# hat.net
KiCad netlist of a schematic drawn in EAGLE
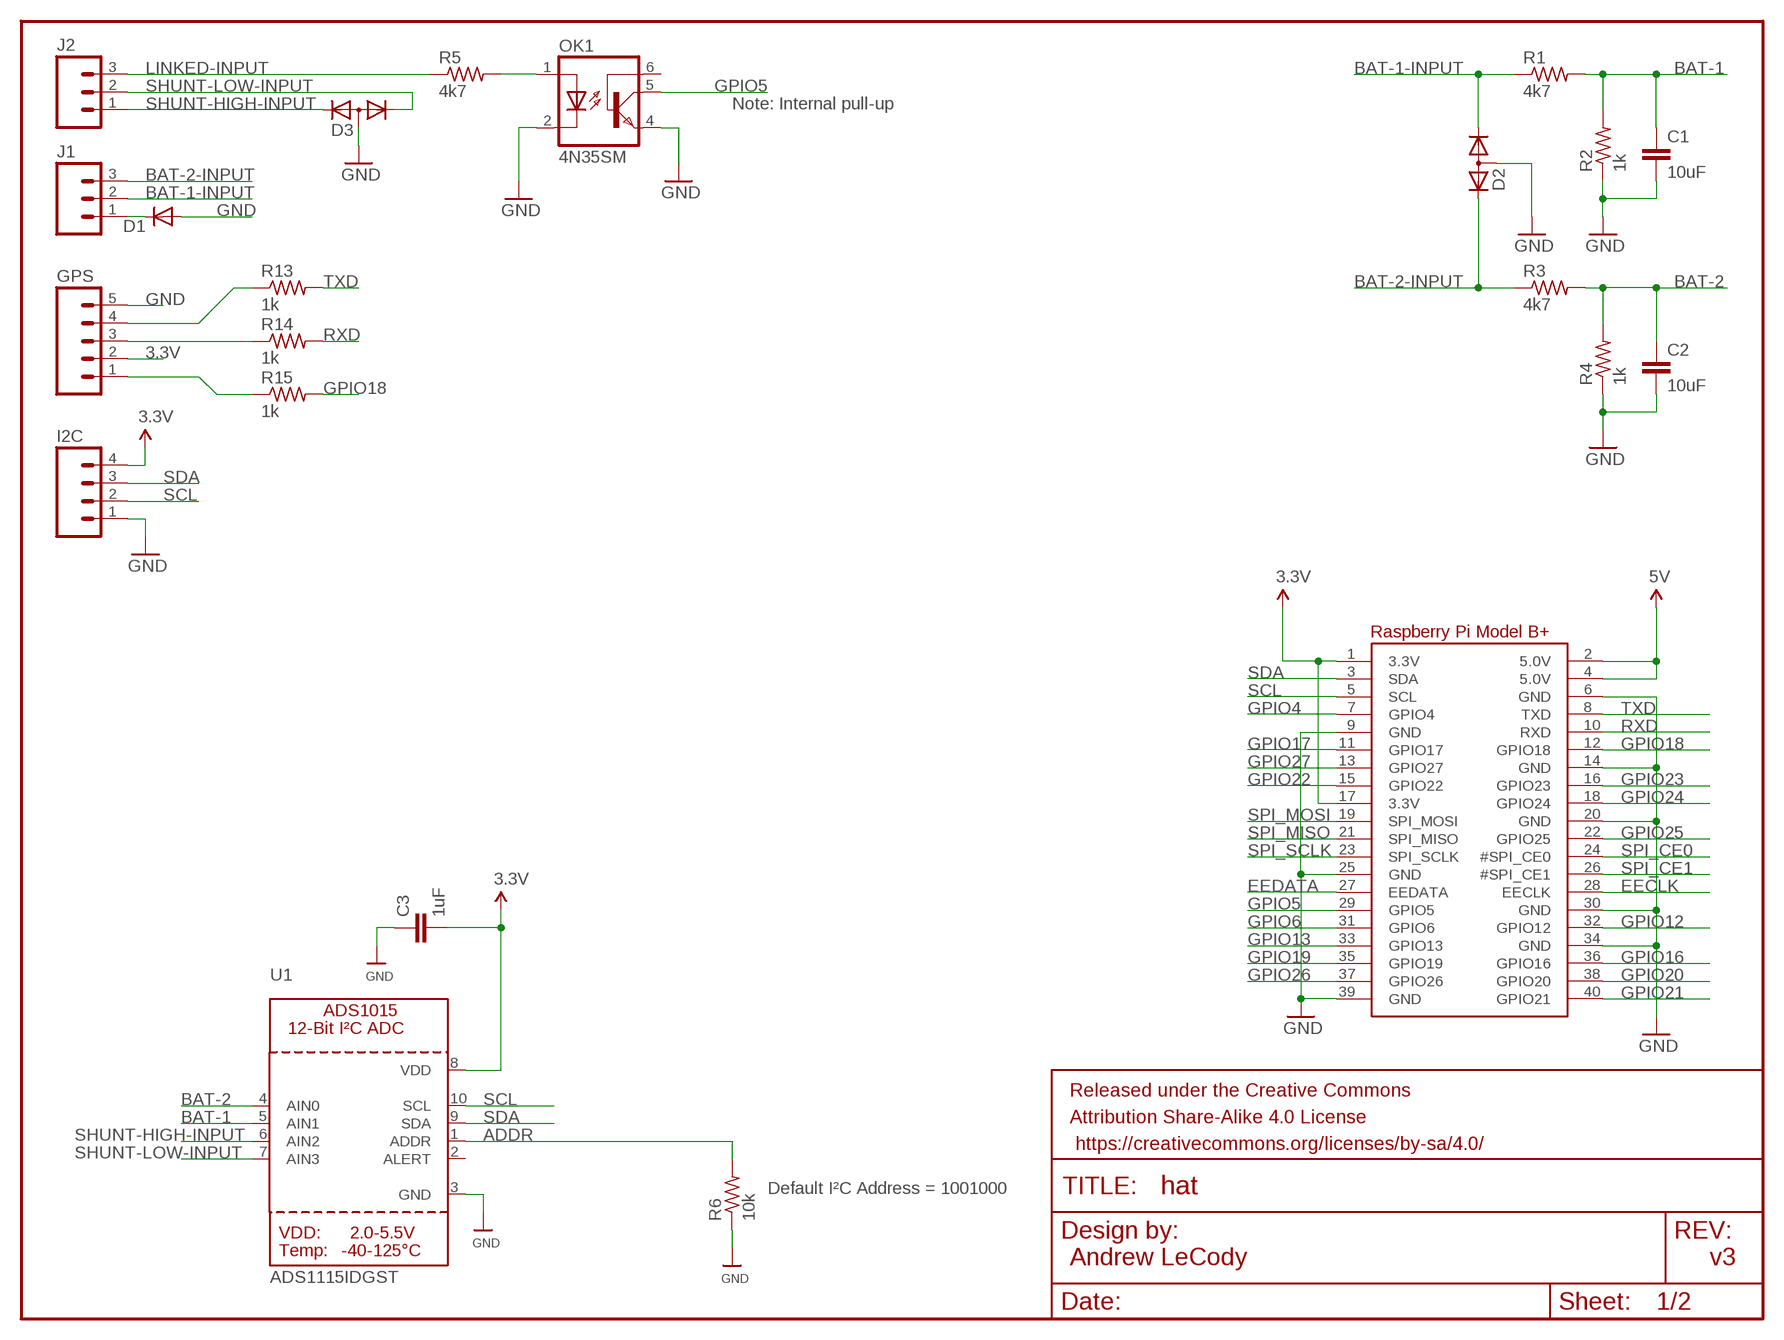
[diagram p0: schematic, sheet 1]
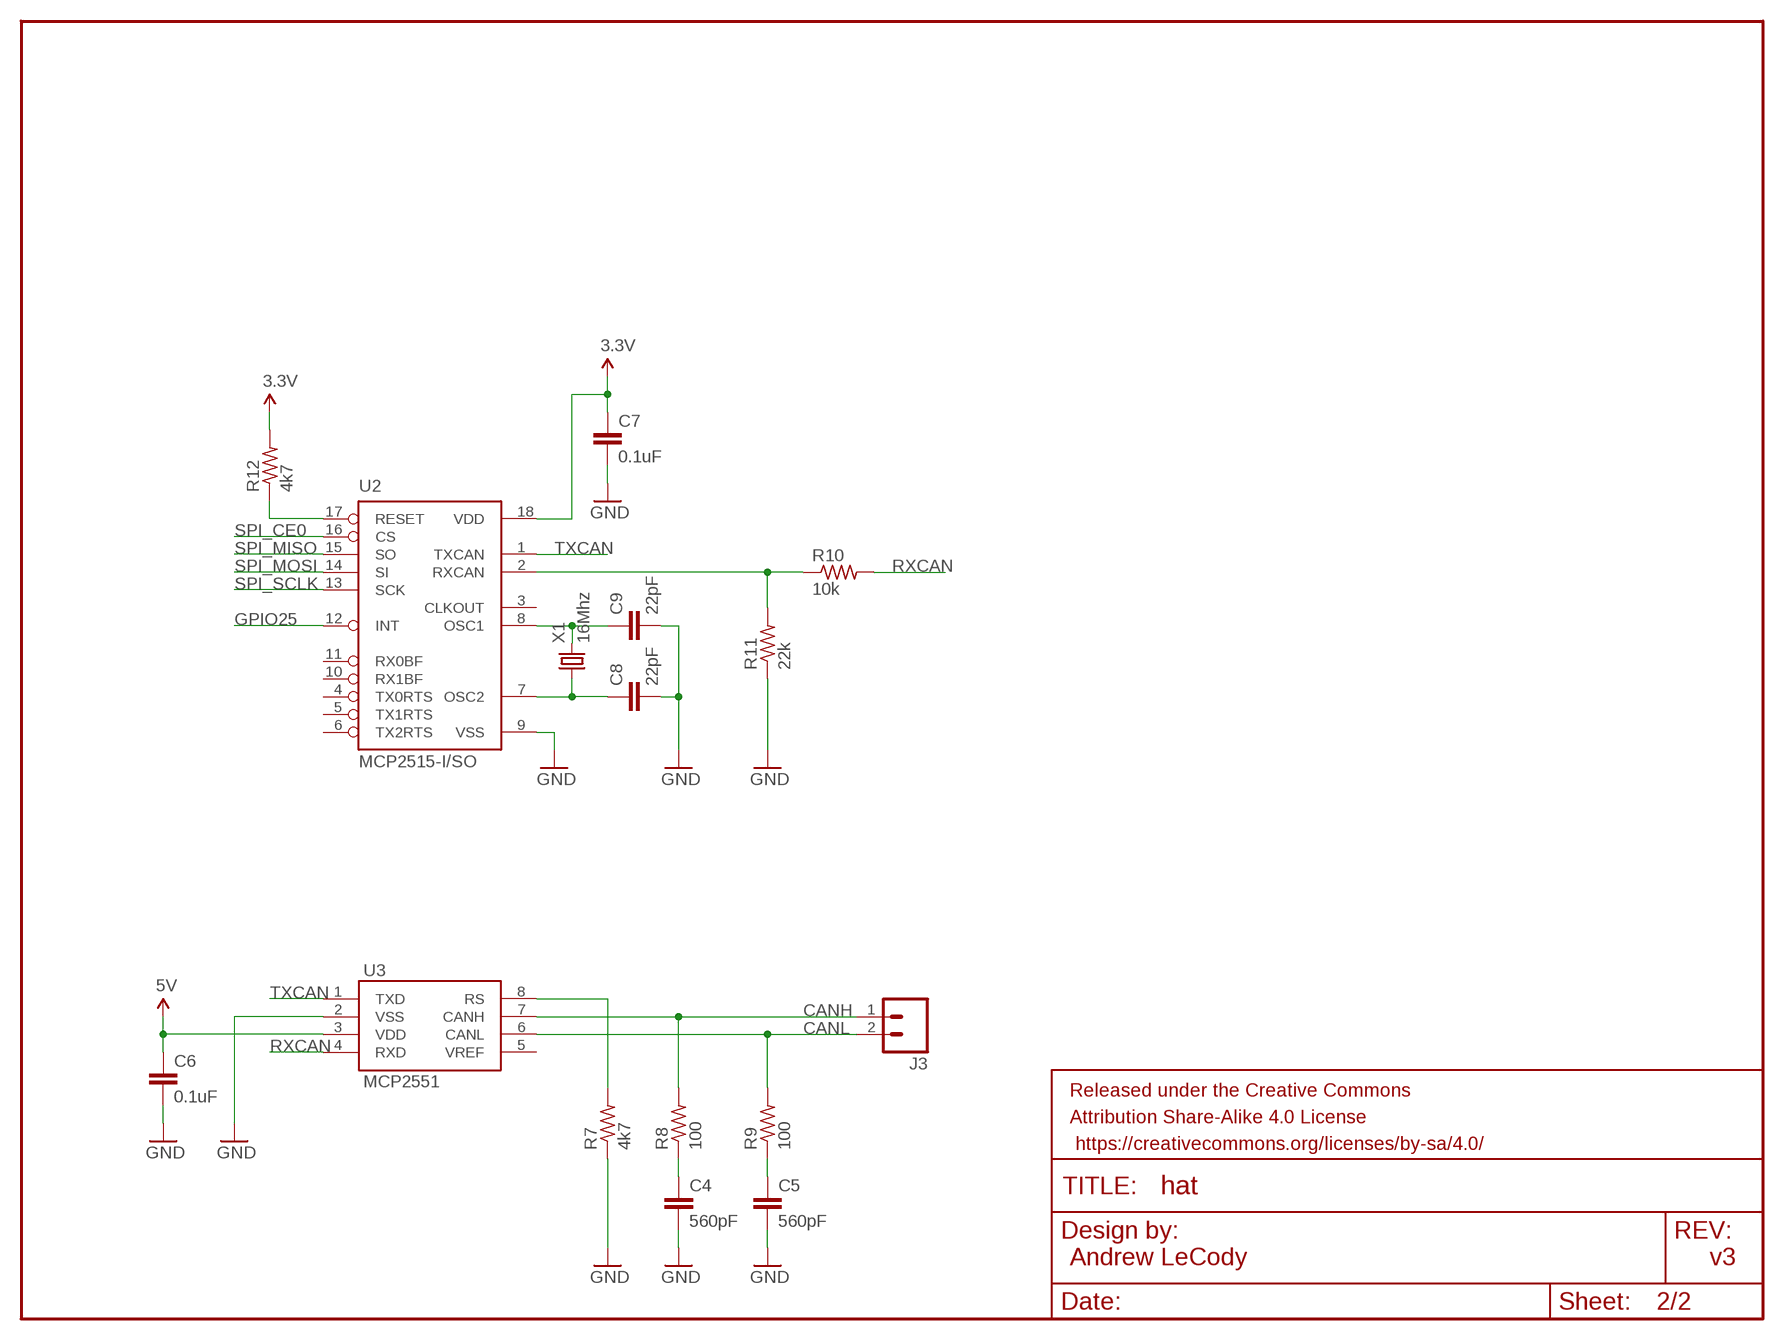
[diagram p1: schematic, sheet 2]

(export (version "E")
  (design (tool "Eeschema 10.0.6"))
  (components
    (comp (ref "C1")
      (value "10uF")
      (footprint "eagle-import:C0805")
      (libsource (lib "eagle-import") (part "CAPACITOR_C0805"))
    )
    (comp (ref "C2")
      (value "10uF")
      (footprint "eagle-import:C0805")
      (libsource (lib "eagle-import") (part "CAPACITOR_C0805"))
    )
    (comp (ref "C3")
      (value "1uF")
      (footprint "eagle-import:C0805")
      (libsource (lib "eagle-import") (part "CAPACITOR_C0805"))
    )
    (comp (ref "D1")
      (value "DIODE-DO214AC")
      (footprint "eagle-import:DO214AC")
      (libsource (lib "eagle-import") (part "DIODE-DO214AC"))
    )
    (comp (ref "D2")
      (value "DIODE-2CA|ACSOT23")
      (footprint "eagle-import:SOT23")
      (libsource (lib "eagle-import") (part "DIODE-2CA|ACSOT23"))
    )
    (comp (ref "D3")
      (value "DIODE-2CA|ACSOT23")
      (footprint "eagle-import:SOT23")
      (libsource (lib "eagle-import") (part "DIODE-2CA|ACSOT23"))
    )
    (comp (ref "FRAME1")
      (value "FRAME-LETTERNO_PACKAGE")
      (footprint "eagle-import:DUMMY")
      (fields (field (name "DESIGNER") "Nobody"))
      (libsource (lib "eagle-import") (part "FRAME-LETTERNO_PACKAGE"))
    )
    (comp (ref "GPS")
      (value "M05PTH")
      (footprint "eagle-import:1X05")
      (libsource (lib "eagle-import") (part "M05PTH"))
    )
    (comp (ref "I2C")
      (value "M04PTH")
      (footprint "eagle-import:1X04")
      (libsource (lib "eagle-import") (part "M04PTH"))
    )
    (comp (ref "J1")
      (value "M03SCREW")
      (footprint "eagle-import:SCREWTERMINAL-3.5MM-3")
      (libsource (lib "eagle-import") (part "M03SCREW"))
    )
    (comp (ref "J2")
      (value "M03SCREW")
      (footprint "eagle-import:SCREWTERMINAL-3.5MM-3")
      (libsource (lib "eagle-import") (part "M03SCREW"))
    )
    (comp (ref "OK1")
      (value "4N35SM")
      (footprint "eagle-import:DIL6-SMD")
      (fields (field (name "MF") "FAIRCHILD SEMICONDUCTOR") (field (name "MPN") "4N35S-M"))
      (libsource (lib "eagle-import") (part "4N?MS35"))
    )
    (comp (ref "R1")
      (value "4k7")
      (footprint "eagle-import:R0805")
      (libsource (lib "eagle-import") (part "aceat64-resistor_RESISTOR_R0805"))
    )
    (comp (ref "R2")
      (value "1k")
      (footprint "eagle-import:R0805")
      (libsource (lib "eagle-import") (part "aceat64-resistor_RESISTOR_R0805"))
    )
    (comp (ref "R3")
      (value "4k7")
      (footprint "eagle-import:R0805")
      (libsource (lib "eagle-import") (part "aceat64-resistor_RESISTOR_R0805"))
    )
    (comp (ref "R4")
      (value "1k")
      (footprint "eagle-import:R0805")
      (libsource (lib "eagle-import") (part "aceat64-resistor_RESISTOR_R0805"))
    )
    (comp (ref "R5")
      (value "4k7")
      (footprint "eagle-import:R0805")
      (libsource (lib "eagle-import") (part "RESISTOR_R0805"))
    )
    (comp (ref "R6")
      (value "10k")
      (footprint "eagle-import:R0805")
      (libsource (lib "eagle-import") (part "RESISTOR_R0805"))
    )
    (comp (ref "R13")
      (value "1k")
      (footprint "eagle-import:R0805")
      (libsource (lib "eagle-import") (part "RESISTOR_R0805"))
    )
    (comp (ref "R14")
      (value "1k")
      (footprint "eagle-import:R0805")
      (libsource (lib "eagle-import") (part "RESISTOR_R0805"))
    )
    (comp (ref "R15")
      (value "1k")
      (footprint "eagle-import:R0805")
      (libsource (lib "eagle-import") (part "RESISTOR_R0805"))
    )
    (comp (ref "RPI1")
      (value "RASPBERRYPI_BPLUS_HATNOSLOTS")
      (footprint "eagle-import:PI_HAT_NOSLOTS")
      (libsource (lib "eagle-import") (part "RASPBERRYPI_BPLUS_HATNOSLOTS"))
    )
    (comp (ref "U1")
      (value "ADS1115IDGST")
      (footprint "eagle-import:MSOP10")
      (libsource (lib "eagle-import") (part "ADC_ADS1015"))
    )
    (comp (ref "C4")
      (value "560pF")
      (footprint "eagle-import:C0805")
      (libsource (lib "eagle-import") (part "CAPACITOR_C0805"))
    )
    (comp (ref "C5")
      (value "560pF")
      (footprint "eagle-import:C0805")
      (libsource (lib "eagle-import") (part "CAPACITOR_C0805"))
    )
    (comp (ref "C6")
      (value "0.1uF")
      (footprint "eagle-import:C0805")
      (libsource (lib "eagle-import") (part "CAPACITOR_C0805"))
    )
    (comp (ref "C7")
      (value "0.1uF")
      (footprint "eagle-import:C0805")
      (libsource (lib "eagle-import") (part "CAPACITOR_C0805"))
    )
    (comp (ref "C8")
      (value "22pF")
      (footprint "eagle-import:C0805")
      (libsource (lib "eagle-import") (part "CAPACITOR_C0805"))
    )
    (comp (ref "C9")
      (value "22pF")
      (footprint "eagle-import:C0805")
      (libsource (lib "eagle-import") (part "CAPACITOR_C0805"))
    )
    (comp (ref "FRAME2")
      (value "FRAME-LETTERNO_PACKAGE")
      (footprint "eagle-import:DUMMY")
      (fields (field (name "DESIGNER") "Nobody"))
      (libsource (lib "eagle-import") (part "FRAME-LETTERNO_PACKAGE"))
    )
    (comp (ref "J3")
      (value "M023.5MM")
      (footprint "eagle-import:SCREWTERMINAL-3.5MM-2")
      (libsource (lib "eagle-import") (part "M023.5MM"))
    )
    (comp (ref "R7")
      (value "4k7")
      (footprint "eagle-import:R0805")
      (libsource (lib "eagle-import") (part "RESISTOR_R0805"))
    )
    (comp (ref "R8")
      (value "100")
      (footprint "eagle-import:R0805")
      (libsource (lib "eagle-import") (part "RESISTOR_R0805"))
    )
    (comp (ref "R9")
      (value "100")
      (footprint "eagle-import:R0805")
      (libsource (lib "eagle-import") (part "RESISTOR_R0805"))
    )
    (comp (ref "R10")
      (value "10k")
      (footprint "eagle-import:R0805")
      (libsource (lib "eagle-import") (part "RESISTOR_R0805"))
    )
    (comp (ref "R11")
      (value "22k")
      (footprint "eagle-import:R0805")
      (libsource (lib "eagle-import") (part "RESISTOR_R0805"))
    )
    (comp (ref "R12")
      (value "4k7")
      (footprint "eagle-import:R0805")
      (libsource (lib "eagle-import") (part "RESISTOR_R0805"))
    )
    (comp (ref "U2")
      (value "MCP2515-I/SO")
      (footprint "eagle-import:SO18L")
      (libsource (lib "eagle-import") (part "MCP2515-I/SO"))
    )
    (comp (ref "U3")
      (value "MCP2551")
      (footprint "eagle-import:SO08")
      (libsource (lib "eagle-import") (part "MCP2551"))
    )
    (comp (ref "X1")
      (value "16Mhz")
      (footprint "eagle-import:HC49-4-HSMX")
      (libsource (lib "eagle-import") (part "CRYSTALS-NOGND-4-HSMX"))
    )
  )
  (nets
    (net (code "1") (name "3.3V") (class "Default")
      (node (ref "C3") (pin "2") (pinfunction "2_2") (pintype "passive"))
      (node (ref "C7") (pin "1") (pinfunction "1_1") (pintype "passive"))
      (node (ref "GPS") (pin "2") (pinfunction "2_2") (pintype "passive"))
      (node (ref "I2C") (pin "4") (pinfunction "4_4") (pintype "passive"))
      (node (ref "R12") (pin "2") (pinfunction "2_2") (pintype "passive"))
      (node (ref "RPI1") (pin "1") (pinfunction "3.3V_1") (pintype "power_in"))
      (node (ref "RPI1") (pin "17") (pinfunction "3.3V_17") (pintype "power_in"))
      (node (ref "U1") (pin "8") (pinfunction "VDD_8") (pintype "bidirectional"))
      (node (ref "U2") (pin "18") (pinfunction "VDD_18") (pintype "power_in"))
    )
    (net (code "2") (name "5V") (class "Default")
      (node (ref "C6") (pin "1") (pinfunction "1_1") (pintype "passive"))
      (node (ref "RPI1") (pin "2") (pinfunction "5.0V_2") (pintype "power_in"))
      (node (ref "RPI1") (pin "4") (pinfunction "5.0V_4") (pintype "power_in"))
      (node (ref "U3") (pin "3") (pinfunction "VDD_3") (pintype "bidirectional"))
    )
    (net (code "3") (name "ADDR") (class "Default")
      (node (ref "R6") (pin "2") (pinfunction "2_2") (pintype "passive"))
      (node (ref "U1") (pin "1") (pinfunction "ADDR_1") (pintype "bidirectional"))
    )
    (net (code "4") (name "BAT-1") (class "Default")
      (node (ref "C1") (pin "1") (pinfunction "1_1") (pintype "passive"))
      (node (ref "R1") (pin "2") (pinfunction "2_2") (pintype "passive"))
      (node (ref "R2") (pin "2") (pinfunction "2_2") (pintype "passive"))
      (node (ref "U1") (pin "5") (pinfunction "AIN1_5") (pintype "bidirectional"))
    )
    (net (code "5") (name "BAT-1-INPUT") (class "Default")
      (node (ref "D2") (pin "1") (pinfunction "K1_1") (pintype "passive"))
      (node (ref "J1") (pin "2") (pinfunction "2_2") (pintype "passive"))
      (node (ref "R1") (pin "1") (pinfunction "1_1") (pintype "passive"))
    )
    (net (code "6") (name "BAT-2") (class "Default")
      (node (ref "C2") (pin "1") (pinfunction "1_1") (pintype "passive"))
      (node (ref "R3") (pin "2") (pinfunction "2_2") (pintype "passive"))
      (node (ref "R4") (pin "2") (pinfunction "2_2") (pintype "passive"))
      (node (ref "U1") (pin "4") (pinfunction "AIN0_4") (pintype "bidirectional"))
    )
    (net (code "7") (name "BAT-2-INPUT") (class "Default")
      (node (ref "D2") (pin "2") (pinfunction "K2_2") (pintype "passive"))
      (node (ref "J1") (pin "3") (pinfunction "3_3") (pintype "passive"))
      (node (ref "R3") (pin "1") (pinfunction "1_1") (pintype "passive"))
    )
    (net (code "8") (name "CANH") (class "Default")
      (node (ref "J3") (pin "1") (pinfunction "1_1") (pintype "passive"))
      (node (ref "R8") (pin "2") (pinfunction "2_2") (pintype "passive"))
      (node (ref "U3") (pin "7") (pinfunction "CANH_7") (pintype "bidirectional"))
    )
    (net (code "9") (name "CANL") (class "Default")
      (node (ref "J3") (pin "2") (pinfunction "2_2") (pintype "passive"))
      (node (ref "R9") (pin "2") (pinfunction "2_2") (pintype "passive"))
      (node (ref "U3") (pin "6") (pinfunction "CANL_6") (pintype "bidirectional"))
    )
    (net (code "10") (name "EECLK") (class "Default")
      (node (ref "RPI1") (pin "28") (pinfunction "EECLK_28") (pintype "power_in"))
    )
    (net (code "11") (name "EEDATA") (class "Default")
      (node (ref "RPI1") (pin "27") (pinfunction "EEDATA_27") (pintype "bidirectional"))
    )
    (net (code "12") (name "GND") (class "Default")
      (node (ref "C1") (pin "2") (pinfunction "2_2") (pintype "passive"))
      (node (ref "C2") (pin "2") (pinfunction "2_2") (pintype "passive"))
      (node (ref "C3") (pin "1") (pinfunction "1_1") (pintype "passive"))
      (node (ref "C4") (pin "2") (pinfunction "2_2") (pintype "passive"))
      (node (ref "C5") (pin "2") (pinfunction "2_2") (pintype "passive"))
      (node (ref "C6") (pin "2") (pinfunction "2_2") (pintype "passive"))
      (node (ref "C7") (pin "2") (pinfunction "2_2") (pintype "passive"))
      (node (ref "C8") (pin "2") (pinfunction "2_2") (pintype "passive"))
      (node (ref "C9") (pin "2") (pinfunction "2_2") (pintype "passive"))
      (node (ref "D1") (pin "A") (pinfunction "A_A") (pintype "passive"))
      (node (ref "D2") (pin "3") (pinfunction "A_3") (pintype "passive"))
      (node (ref "D3") (pin "3") (pinfunction "A_3") (pintype "passive"))
      (node (ref "GPS") (pin "5") (pinfunction "5_5") (pintype "passive"))
      (node (ref "I2C") (pin "1") (pinfunction "1_1") (pintype "passive"))
      (node (ref "OK1") (pin "2") (pinfunction "C_2") (pintype "passive"))
      (node (ref "OK1") (pin "4") (pinfunction "EMI_4") (pintype "passive"))
      (node (ref "R11") (pin "1") (pinfunction "1_1") (pintype "passive"))
      (node (ref "R2") (pin "1") (pinfunction "1_1") (pintype "passive"))
      (node (ref "R4") (pin "1") (pinfunction "1_1") (pintype "passive"))
      (node (ref "R6") (pin "1") (pinfunction "1_1") (pintype "passive"))
      (node (ref "R7") (pin "1") (pinfunction "1_1") (pintype "passive"))
      (node (ref "RPI1") (pin "14") (pinfunction "GND_14") (pintype "power_in"))
      (node (ref "RPI1") (pin "20") (pinfunction "GND_20") (pintype "power_in"))
      (node (ref "RPI1") (pin "25") (pinfunction "GND_25") (pintype "power_in"))
      (node (ref "RPI1") (pin "30") (pinfunction "GND_30") (pintype "bidirectional"))
      (node (ref "RPI1") (pin "34") (pinfunction "GND_34") (pintype "bidirectional"))
      (node (ref "RPI1") (pin "39") (pinfunction "GND_39") (pintype "power_in"))
      (node (ref "RPI1") (pin "6") (pinfunction "GND_6") (pintype "power_in"))
      (node (ref "RPI1") (pin "9") (pinfunction "GND_9") (pintype "power_in"))
      (node (ref "U1") (pin "3") (pinfunction "GND_3") (pintype "bidirectional"))
      (node (ref "U2") (pin "9") (pinfunction "VSS_9") (pintype "power_in"))
      (node (ref "U3") (pin "2") (pinfunction "VSS_2") (pintype "bidirectional"))
    )
    (net (code "13") (name "GPIO4") (class "Default")
      (node (ref "RPI1") (pin "7") (pinfunction "GPIO4_7") (pintype "bidirectional"))
    )
    (net (code "14") (name "GPIO5") (class "Default")
      (node (ref "OK1") (pin "5") (pinfunction "COL_5") (pintype "passive"))
      (node (ref "RPI1") (pin "29") (pinfunction "GPIO5_29") (pintype "bidirectional"))
    )
    (net (code "15") (name "GPIO6") (class "Default")
      (node (ref "RPI1") (pin "31") (pinfunction "GPIO6_31") (pintype "power_in"))
    )
    (net (code "16") (name "GPIO12") (class "Default")
      (node (ref "RPI1") (pin "32") (pinfunction "GPIO12_32") (pintype "bidirectional"))
    )
    (net (code "17") (name "GPIO13") (class "Default")
      (node (ref "RPI1") (pin "33") (pinfunction "GPIO13_33") (pintype "bidirectional"))
    )
    (net (code "18") (name "GPIO16") (class "Default")
      (node (ref "RPI1") (pin "36") (pinfunction "GPIO16_36") (pintype "power_in"))
    )
    (net (code "19") (name "GPIO17") (class "Default")
      (node (ref "RPI1") (pin "11") (pinfunction "GPIO17_11") (pintype "bidirectional"))
    )
    (net (code "20") (name "GPIO18") (class "Default")
      (node (ref "R15") (pin "2") (pinfunction "2_2") (pintype "passive"))
      (node (ref "RPI1") (pin "12") (pinfunction "GPIO18_12") (pintype "bidirectional"))
    )
    (net (code "21") (name "GPIO19") (class "Default")
      (node (ref "RPI1") (pin "35") (pinfunction "GPIO19_35") (pintype "bidirectional"))
    )
    (net (code "22") (name "GPIO20") (class "Default")
      (node (ref "RPI1") (pin "38") (pinfunction "GPIO20_38") (pintype "bidirectional"))
    )
    (net (code "23") (name "GPIO21") (class "Default")
      (node (ref "RPI1") (pin "40") (pinfunction "GPIO21_40") (pintype "bidirectional"))
    )
    (net (code "24") (name "GPIO22") (class "Default")
      (node (ref "RPI1") (pin "15") (pinfunction "GPIO22_15") (pintype "bidirectional"))
    )
    (net (code "25") (name "GPIO23") (class "Default")
      (node (ref "RPI1") (pin "16") (pinfunction "GPIO23_16") (pintype "bidirectional"))
    )
    (net (code "26") (name "GPIO24") (class "Default")
      (node (ref "RPI1") (pin "18") (pinfunction "GPIO24_18") (pintype "bidirectional"))
    )
    (net (code "27") (name "GPIO25") (class "Default")
      (node (ref "RPI1") (pin "22") (pinfunction "GPIO25_22") (pintype "bidirectional"))
      (node (ref "U2") (pin "12") (pinfunction "INT_12") (pintype "output"))
    )
    (net (code "28") (name "GPIO26") (class "Default")
      (node (ref "RPI1") (pin "37") (pinfunction "GPIO26_37") (pintype "bidirectional"))
    )
    (net (code "29") (name "GPIO27") (class "Default")
      (node (ref "RPI1") (pin "13") (pinfunction "GPIO27_13") (pintype "bidirectional"))
    )
    (net (code "30") (name "LINKED-INPUT") (class "Default")
      (node (ref "J2") (pin "3") (pinfunction "3_3") (pintype "passive"))
      (node (ref "R5") (pin "1") (pinfunction "1_1") (pintype "passive"))
    )
    (net (code "31") (name "Net-(C4-Pad1)") (class "Default")
      (node (ref "C4") (pin "1") (pinfunction "1_1") (pintype "passive"))
      (node (ref "R8") (pin "1") (pinfunction "1_1") (pintype "passive"))
    )
    (net (code "32") (name "Net-(C5-Pad1)") (class "Default")
      (node (ref "C5") (pin "1") (pinfunction "1_1") (pintype "passive"))
      (node (ref "R9") (pin "1") (pinfunction "1_1") (pintype "passive"))
    )
    (net (code "33") (name "Net-(D1-PadC)") (class "Default")
      (node (ref "D1") (pin "C") (pinfunction "C_C") (pintype "passive"))
      (node (ref "J1") (pin "1") (pinfunction "1_1") (pintype "passive"))
    )
    (net (code "34") (name "Net-(GPS-Pad1)") (class "Default")
      (node (ref "GPS") (pin "1") (pinfunction "1_1") (pintype "passive"))
      (node (ref "R15") (pin "1") (pinfunction "1_1") (pintype "passive"))
    )
    (net (code "35") (name "Net-(GPS-Pad3)") (class "Default")
      (node (ref "GPS") (pin "3") (pinfunction "3_3") (pintype "passive"))
      (node (ref "R14") (pin "1") (pinfunction "1_1") (pintype "passive"))
    )
    (net (code "36") (name "Net-(GPS-Pad4)") (class "Default")
      (node (ref "GPS") (pin "4") (pinfunction "4_4") (pintype "passive"))
      (node (ref "R13") (pin "1") (pinfunction "1_1") (pintype "passive"))
    )
    (net (code "37") (name "Net-(OK1-A)") (class "Default")
      (node (ref "OK1") (pin "1") (pinfunction "A_1") (pintype "passive"))
      (node (ref "R5") (pin "2") (pinfunction "2_2") (pintype "passive"))
    )
    (net (code "38") (name "Net-(U2-OSC1)") (class "Default")
      (node (ref "C9") (pin "1") (pinfunction "1_1") (pintype "passive"))
      (node (ref "U2") (pin "8") (pinfunction "OSC1_8") (pintype "input"))
      (node (ref "X1") (pin "2") (pinfunction "2_2") (pintype "passive"))
    )
    (net (code "39") (name "Net-(U2-OSC2)") (class "Default")
      (node (ref "C8") (pin "1") (pinfunction "1_1") (pintype "passive"))
      (node (ref "U2") (pin "7") (pinfunction "OSC2_7") (pintype "output"))
      (node (ref "X1") (pin "1") (pinfunction "1_1") (pintype "passive"))
    )
    (net (code "40") (name "Net-(U2-RESET)") (class "Default")
      (node (ref "R12") (pin "1") (pinfunction "1_1") (pintype "passive"))
      (node (ref "U2") (pin "17") (pinfunction "RESET_17") (pintype "input"))
    )
    (net (code "41") (name "Net-(U2-RXCAN)") (class "Default")
      (node (ref "R10") (pin "1") (pinfunction "1_1") (pintype "passive"))
      (node (ref "R11") (pin "2") (pinfunction "2_2") (pintype "passive"))
      (node (ref "U2") (pin "2") (pinfunction "RXCAN_2") (pintype "input"))
    )
    (net (code "42") (name "Net-(U3-RS)") (class "Default")
      (node (ref "R7") (pin "2") (pinfunction "2_2") (pintype "passive"))
      (node (ref "U3") (pin "8") (pinfunction "RS_8") (pintype "bidirectional"))
    )
    (net (code "43") (name "RXCAN") (class "Default")
      (node (ref "R10") (pin "2") (pinfunction "2_2") (pintype "passive"))
      (node (ref "U3") (pin "4") (pinfunction "RXD_4") (pintype "bidirectional"))
    )
    (net (code "44") (name "RXD") (class "Default")
      (node (ref "R14") (pin "2") (pinfunction "2_2") (pintype "passive"))
      (node (ref "RPI1") (pin "10") (pinfunction "RXD_10") (pintype "bidirectional"))
    )
    (net (code "45") (name "SCL") (class "Default")
      (node (ref "I2C") (pin "2") (pinfunction "2_2") (pintype "passive"))
      (node (ref "RPI1") (pin "5") (pinfunction "SCL_5") (pintype "bidirectional"))
      (node (ref "U1") (pin "10") (pinfunction "SCL_10") (pintype "bidirectional"))
    )
    (net (code "46") (name "SDA") (class "Default")
      (node (ref "I2C") (pin "3") (pinfunction "3_3") (pintype "passive"))
      (node (ref "RPI1") (pin "3") (pinfunction "SDA_3") (pintype "bidirectional"))
      (node (ref "U1") (pin "9") (pinfunction "SDA_9") (pintype "bidirectional"))
    )
    (net (code "47") (name "SHUNT-HIGH-INPUT") (class "Default")
      (node (ref "D3") (pin "2") (pinfunction "K2_2") (pintype "passive"))
      (node (ref "J2") (pin "1") (pinfunction "1_1") (pintype "passive"))
      (node (ref "U1") (pin "6") (pinfunction "AIN2_6") (pintype "bidirectional"))
    )
    (net (code "48") (name "SHUNT-LOW-INPUT") (class "Default")
      (node (ref "D3") (pin "1") (pinfunction "K1_1") (pintype "passive"))
      (node (ref "J2") (pin "2") (pinfunction "2_2") (pintype "passive"))
      (node (ref "U1") (pin "7") (pinfunction "AIN3_7") (pintype "bidirectional"))
    )
    (net (code "49") (name "SPI_CE0") (class "Default")
      (node (ref "RPI1") (pin "24") (pinfunction "#SPI_CE0_24") (pintype "bidirectional"))
      (node (ref "U2") (pin "16") (pinfunction "CS_16") (pintype "input"))
    )
    (net (code "50") (name "SPI_CE1") (class "Default")
      (node (ref "RPI1") (pin "26") (pinfunction "#SPI_CE1_26") (pintype "bidirectional"))
    )
    (net (code "51") (name "SPI_MISO") (class "Default")
      (node (ref "RPI1") (pin "21") (pinfunction "SPI_MISO_21") (pintype "bidirectional"))
      (node (ref "U2") (pin "15") (pinfunction "SO_15") (pintype "output"))
    )
    (net (code "52") (name "SPI_MOSI") (class "Default")
      (node (ref "RPI1") (pin "19") (pinfunction "SPI_MOSI_19") (pintype "bidirectional"))
      (node (ref "U2") (pin "14") (pinfunction "SI_14") (pintype "input"))
    )
    (net (code "53") (name "SPI_SCLK") (class "Default")
      (node (ref "RPI1") (pin "23") (pinfunction "SPI_SCLK_23") (pintype "bidirectional"))
      (node (ref "U2") (pin "13") (pinfunction "SCK_13") (pintype "input"))
    )
    (net (code "54") (name "TXCAN") (class "Default")
      (node (ref "U2") (pin "1") (pinfunction "TXCAN_1") (pintype "output"))
      (node (ref "U3") (pin "1") (pinfunction "TXD_1") (pintype "bidirectional"))
    )
    (net (code "55") (name "TXD") (class "Default")
      (node (ref "R13") (pin "2") (pinfunction "2_2") (pintype "passive"))
      (node (ref "RPI1") (pin "8") (pinfunction "TXD_8") (pintype "output"))
    )
    (net (code "56") (name "unconnected-(OK1-BAS-Pad6)") (class "Default")
      (node (ref "OK1") (pin "6") (pinfunction "BAS_6") (pintype "passive"))
    )
    (net (code "57") (name "unconnected-(U1-ALERT-Pad2)") (class "Default")
      (node (ref "U1") (pin "2") (pinfunction "ALERT_2") (pintype "bidirectional"))
    )
    (net (code "58") (name "unconnected-(U2-CLKOUT-Pad3)") (class "Default")
      (node (ref "U2") (pin "3") (pinfunction "CLKOUT_3") (pintype "output"))
    )
    (net (code "59") (name "unconnected-(U2-RX0BF-Pad11)") (class "Default")
      (node (ref "U2") (pin "11") (pinfunction "RX0BF_11") (pintype "output"))
    )
    (net (code "60") (name "unconnected-(U2-RX1BF-Pad10)") (class "Default")
      (node (ref "U2") (pin "10") (pinfunction "RX1BF_10") (pintype "output"))
    )
    (net (code "61") (name "unconnected-(U2-TX0RTS-Pad4)") (class "Default")
      (node (ref "U2") (pin "4") (pinfunction "TX0RTS_4") (pintype "input"))
    )
    (net (code "62") (name "unconnected-(U2-TX1RTS-Pad5)") (class "Default")
      (node (ref "U2") (pin "5") (pinfunction "TX1RTS_5") (pintype "input"))
    )
    (net (code "63") (name "unconnected-(U2-TX2RTS-Pad6)") (class "Default")
      (node (ref "U2") (pin "6") (pinfunction "TX2RTS_6") (pintype "input"))
    )
    (net (code "64") (name "unconnected-(U3-VREF-Pad5)") (class "Default")
      (node (ref "U3") (pin "5") (pinfunction "VREF_5") (pintype "bidirectional"))
    )
  )
)
